# comms_sys_schematic_V2.net
KiCad netlist of a schematic drawn in EAGLE
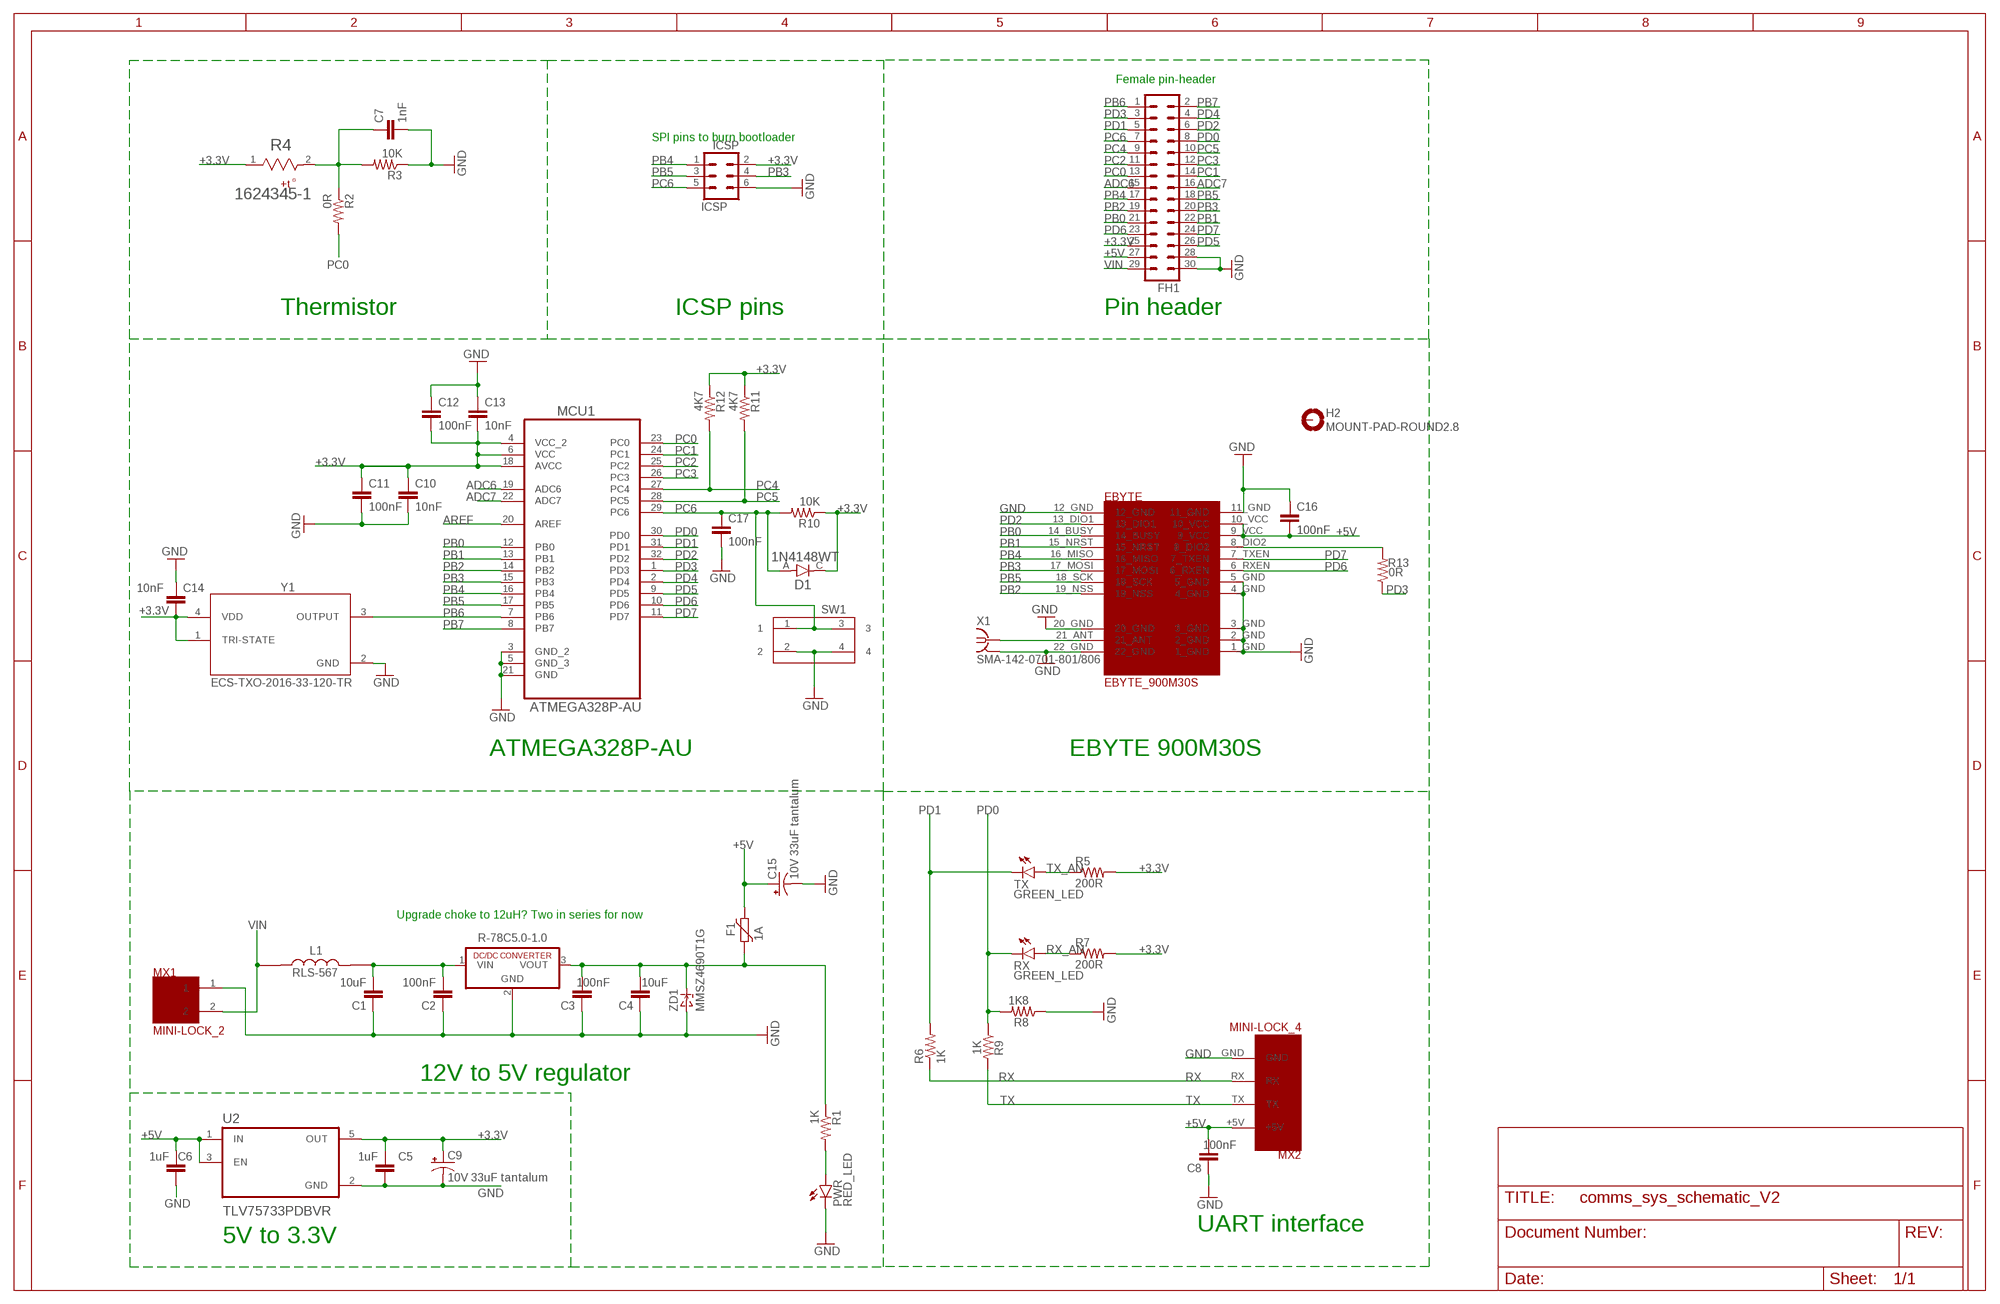
[diagram p0: schematic, sheet 1]

(export (version "E")
  (design (tool "Eeschema 10.0.6"))
  (components
    (comp (ref "C1")
      (value "10uF")
      (footprint "eagle-import:C0805")
      (libsource (lib "eagle-import") (part "C-EUC0805"))
    )
    (comp (ref "C2")
      (value "100nF")
      (footprint "eagle-import:C0805")
      (libsource (lib "eagle-import") (part "C-EUC0805"))
    )
    (comp (ref "C3")
      (value "100nF")
      (footprint "eagle-import:C0805")
      (libsource (lib "eagle-import") (part "C-EUC0805"))
    )
    (comp (ref "C4")
      (value "10uF")
      (footprint "eagle-import:C0805")
      (libsource (lib "eagle-import") (part "C-EUC0805"))
    )
    (comp (ref "C5")
      (value "1uF")
      (footprint "eagle-import:C0805")
      (libsource (lib "eagle-import") (part "C-EUC0805"))
    )
    (comp (ref "C6")
      (value "1uF")
      (footprint "eagle-import:C0805")
      (libsource (lib "eagle-import") (part "C-EUC0805"))
    )
    (comp (ref "C7")
      (value "1nF")
      (footprint "eagle-import:C0805")
      (libsource (lib "eagle-import") (part "C-EUC0805"))
    )
    (comp (ref "C8")
      (value "100nF")
      (footprint "eagle-import:C0805")
      (libsource (lib "eagle-import") (part "C-EUC0805"))
    )
    (comp (ref "C9")
      (value "10V 33uF tantalum")
      (footprint "eagle-import:CT3216")
      (libsource (lib "eagle-import") (part "CPOL-USCT3216"))
    )
    (comp (ref "C10")
      (value "10nF")
      (footprint "eagle-import:C0805")
      (libsource (lib "eagle-import") (part "C-EUC0805"))
    )
    (comp (ref "C11")
      (value "100nF")
      (footprint "eagle-import:C0805")
      (libsource (lib "eagle-import") (part "C-EUC0805"))
    )
    (comp (ref "C12")
      (value "100nF")
      (footprint "eagle-import:C0805")
      (libsource (lib "eagle-import") (part "C-EUC0805"))
    )
    (comp (ref "C13")
      (value "10nF")
      (footprint "eagle-import:C0805")
      (libsource (lib "eagle-import") (part "C-EUC0805"))
    )
    (comp (ref "C14")
      (value "10nF")
      (footprint "eagle-import:C0805")
      (libsource (lib "eagle-import") (part "C-EUC0805"))
    )
    (comp (ref "C15")
      (value "10V 33uF tantalum")
      (footprint "eagle-import:CT3216")
      (libsource (lib "eagle-import") (part "CPOL-USCT3216"))
    )
    (comp (ref "C16")
      (value "100nF")
      (footprint "eagle-import:C0805")
      (libsource (lib "eagle-import") (part "C-EUC0805"))
    )
    (comp (ref "C17")
      (value "100nF")
      (footprint "eagle-import:C0805")
      (libsource (lib "eagle-import") (part "C-EUC0805"))
    )
    (comp (ref "D1")
      (value "1N4148WT")
      (footprint "eagle-import:SODFL1608X70N")
      (fields (field (name "DIGI-KEY_PART_NUMBER") "1N4148WTCT-ND") (field (name "MF") "ON Semiconductor"))
      (libsource (lib "eagle-import") (part "1N4148WT"))
    )
    (comp (ref "EBYTE")
      (value "EBYTE_900M30S")
      (footprint "eagle-import:EBYTE_SX1262_900M30S_FOOTPRINT")
      (libsource (lib "eagle-import") (part "EBYTE_SX1262_900M30S"))
    )
    (comp (ref "F1")
      (value "1A")
      (footprint "eagle-import:PTC0805")
      (libsource (lib "eagle-import") (part "FUSE_PTC-0805"))
    )
    (comp (ref "FH1")
      (value "MA15-2")
      (footprint "eagle-import:MA15-2")
      (libsource (lib "eagle-import") (part "MA15-2"))
    )
    (comp (ref "H2")
      (value "MOUNT-PAD-ROUND2.8")
      (footprint "eagle-import:2,8-PAD")
      (libsource (lib "eagle-import") (part "MOUNT-PAD-ROUND2.8"))
    )
    (comp (ref "ICSP")
      (value "ICSP")
      (footprint "eagle-import:MA03-2")
      (libsource (lib "eagle-import") (part "MA03-2"))
    )
    (comp (ref "L1")
      (value "RLS-567")
      (footprint "eagle-import:IND_RLS-567")
      (fields (field (name "MF") "Recom Power"))
      (libsource (lib "eagle-import") (part "RLS-567"))
    )
    (comp (ref "MCU1")
      (value "ATMEGA328P-AU")
      (footprint "eagle-import:QFP80P900X900X120-32N")
      (libsource (lib "eagle-import") (part "ATMEGA328P-AU"))
    )
    (comp (ref "MX1")
      (value "MINI-LOCK_2")
      (footprint "eagle-import:MINI-LOCK_2")
      (libsource (lib "eagle-import") (part "MINI-LOCK_2"))
    )
    (comp (ref "MX2")
      (value "MINI-LOCK_4")
      (footprint "eagle-import:MINI-LOCK_4")
      (libsource (lib "eagle-import") (part "MINI-LOCK_4"))
    )
    (comp (ref "PWR")
      (value "RED_LED")
      (footprint "eagle-import:CHIP-LED0805")
      (libsource (lib "eagle-import") (part "LEDCHIP-LED0805"))
    )
    (comp (ref "R1")
      (value "1K")
      (footprint "eagle-import:R0805")
      (libsource (lib "eagle-import") (part "R-US_R0805"))
    )
    (comp (ref "R2")
      (value "0R")
      (footprint "eagle-import:R0805")
      (libsource (lib "eagle-import") (part "R-US_R0805"))
    )
    (comp (ref "R3")
      (value "10K")
      (footprint "eagle-import:R0805")
      (libsource (lib "eagle-import") (part "R-US_R0805"))
    )
    (comp (ref "R4")
      (value "1624345-1")
      (footprint "eagle-import:THRMC2012X50N")
      (fields
        (field (name "DIGI-KEY_PART_NUMBER") "A106104CT-ND")
        (field (name "MF") "TE Connectivity")
        (field (name "MP") "NTC0805J10K")
      )
      (libsource (lib "eagle-import") (part "1624345-1"))
    )
    (comp (ref "R5")
      (value "200R")
      (footprint "eagle-import:R0805")
      (libsource (lib "eagle-import") (part "R-US_R0805"))
    )
    (comp (ref "R6")
      (value "1K")
      (footprint "eagle-import:R0805")
      (libsource (lib "eagle-import") (part "R-US_R0805"))
    )
    (comp (ref "R7")
      (value "200R")
      (footprint "eagle-import:R0805")
      (libsource (lib "eagle-import") (part "R-US_R0805"))
    )
    (comp (ref "R8")
      (value "1K8")
      (footprint "eagle-import:R0805")
      (libsource (lib "eagle-import") (part "R-US_R0805"))
    )
    (comp (ref "R9")
      (value "1K")
      (footprint "eagle-import:R0805")
      (libsource (lib "eagle-import") (part "R-US_R0805"))
    )
    (comp (ref "R10")
      (value "10K")
      (footprint "eagle-import:R0805")
      (libsource (lib "eagle-import") (part "R-US_R0805"))
    )
    (comp (ref "R11")
      (value "4K7")
      (footprint "eagle-import:R0805")
      (libsource (lib "eagle-import") (part "R-US_R0805"))
    )
    (comp (ref "R12")
      (value "4K7")
      (footprint "eagle-import:R0805")
      (libsource (lib "eagle-import") (part "R-US_R0805"))
    )
    (comp (ref "R13")
      (value "0R")
      (footprint "eagle-import:R0805")
      (libsource (lib "eagle-import") (part "R-US_R0805"))
    )
    (comp (ref "RX")
      (value "GREEN_LED")
      (footprint "eagle-import:CHIP-LED0805")
      (libsource (lib "eagle-import") (part "LEDCHIP-LED0805"))
    )
    (comp (ref "SW1")
      (value "430152043826")
      (footprint "eagle-import:430152043826")
      (libsource (lib "eagle-import") (part "430152043826"))
    )
    (comp (ref "TX")
      (value "GREEN_LED")
      (footprint "eagle-import:CHIP-LED0805")
      (libsource (lib "eagle-import") (part "LEDCHIP-LED0805"))
    )
    (comp (ref "U1")
      (value "R-78C5.0-1.0")
      (footprint "eagle-import:SIP3")
      (libsource (lib "eagle-import") (part "R-78C-1.05.0"))
    )
    (comp (ref "U2")
      (value "TLV75733PDBVR")
      (footprint "eagle-import:SOT95P280X145-5N")
      (fields (field (name "DIGI-KEY_PART_NUMBER") "296-50414-1-ND") (field (name "MF") "Texas Instruments"))
      (libsource (lib "eagle-import") (part "TLV75733PDBVR"))
    )
    (comp (ref "X1")
      (value "SMA-142-0701-801/806")
      (footprint "eagle-import:J502-ND-142-0701-801_806")
      (fields (field (name "MF") "JOHNSON COMPONENTS") (field (name "MPN") "142-0701-801"))
      (libsource (lib "eagle-import") (part "SMA-142-0701-801/806"))
    )
    (comp (ref "Y1")
      (value "ECS-TXO-2016-33-120-TR")
      (footprint "eagle-import:OSC_ECS-TXO-2016-33-120-TR")
      (fields (field (name "DIGI-KEY_PART_NUMBER") "XC3160CT-ND") (field (name "MF") "ECS Inc."))
      (libsource (lib "eagle-import") (part "ECS-TXO-2016-33-120-TR"))
    )
    (comp (ref "ZD1")
      (value "MMSZ4690T1G")
      (footprint "eagle-import:SOD-123")
      (libsource (lib "eagle-import") (part "ZENERSOD-123"))
    )
  )
  (nets
    (net (code "1") (name "/+3.3V") (class "Default")
      (node (ref "C10") (pin "1") (pinfunction "1_1") (pintype "passive"))
      (node (ref "C11") (pin "1") (pinfunction "1_1") (pintype "passive"))
      (node (ref "C12") (pin "2") (pinfunction "2_2") (pintype "passive"))
      (node (ref "C13") (pin "2") (pinfunction "2_2") (pintype "passive"))
      (node (ref "C14") (pin "2") (pinfunction "2_2") (pintype "passive"))
      (node (ref "C5") (pin "2") (pinfunction "2_2") (pintype "passive"))
      (node (ref "C9") (pin "+") (pinfunction "+_+") (pintype "passive"))
      (node (ref "D1") (pin "C") (pinfunction "C_C") (pintype "passive"))
      (node (ref "FH1") (pin "25") (pinfunction "29_25") (pintype "passive"))
      (node (ref "ICSP") (pin "2") (pinfunction "2_2") (pintype "passive"))
      (node (ref "MCU1") (pin "18") (pinfunction "AVCC_18") (pintype "power_in"))
      (node (ref "MCU1") (pin "4") (pinfunction "VCC_2_4") (pintype "power_in"))
      (node (ref "MCU1") (pin "6") (pinfunction "VCC_6") (pintype "power_in"))
      (node (ref "R10") (pin "1") (pinfunction "1_1") (pintype "passive"))
      (node (ref "R11") (pin "1") (pinfunction "1_1") (pintype "passive"))
      (node (ref "R12") (pin "1") (pinfunction "1_1") (pintype "passive"))
      (node (ref "R4") (pin "1") (pinfunction "1_1") (pintype "passive"))
      (node (ref "R5") (pin "2") (pinfunction "2_2") (pintype "passive"))
      (node (ref "R7") (pin "2") (pinfunction "2_2") (pintype "passive"))
      (node (ref "U2") (pin "5") (pinfunction "OUT_5") (pintype "output"))
      (node (ref "Y1") (pin "1") (pinfunction "TRI-STATE_1") (pintype "input"))
      (node (ref "Y1") (pin "4") (pinfunction "VDD_4") (pintype "input"))
    )
    (net (code "2") (name "/+5V") (class "Default")
      (node (ref "C15") (pin "+") (pinfunction "+_+") (pintype "passive"))
      (node (ref "C16") (pin "2") (pinfunction "2_2") (pintype "passive"))
      (node (ref "C6") (pin "2") (pinfunction "2_2") (pintype "passive"))
      (node (ref "C8") (pin "2") (pinfunction "2_2") (pintype "passive"))
      (node (ref "EBYTE") (pin "10_VCC") (pinfunction "10_VCC_10_VCC") (pintype "power_in"))
      (node (ref "EBYTE") (pin "9_VCC") (pinfunction "9_VCC_9_VCC") (pintype "power_in"))
      (node (ref "F1") (pin "2") (pinfunction "2_2") (pintype "passive"))
      (node (ref "FH1") (pin "27") (pinfunction "31_27") (pintype "passive"))
      (node (ref "MX2") (pin "+5V") (pinfunction "+5V_+5V") (pintype "bidirectional"))
      (node (ref "U2") (pin "1") (pinfunction "IN_1") (pintype "input"))
      (node (ref "U2") (pin "3") (pinfunction "EN_3") (pintype "bidirectional"))
    )
    (net (code "3") (name "/ADC6") (class "Default")
      (node (ref "FH1") (pin "15") (pinfunction "19_15") (pintype "passive"))
      (node (ref "MCU1") (pin "19") (pinfunction "ADC6_19") (pintype "input"))
    )
    (net (code "4") (name "/ADC7") (class "Default")
      (node (ref "FH1") (pin "16") (pinfunction "20_16") (pintype "passive"))
      (node (ref "MCU1") (pin "22") (pinfunction "ADC7_22") (pintype "input"))
    )
    (net (code "5") (name "/AREF") (class "Default")
      (node (ref "MCU1") (pin "20") (pinfunction "AREF_20") (pintype "input"))
    )
    (net (code "6") (name "/PB0") (class "Default")
      (node (ref "EBYTE") (pin "14_BUSY") (pinfunction "14_BUSY_14_BUSY") (pintype "bidirectional"))
      (node (ref "FH1") (pin "21") (pinfunction "25_21") (pintype "passive"))
      (node (ref "MCU1") (pin "12") (pinfunction "PB0_12") (pintype "bidirectional"))
    )
    (net (code "7") (name "/PB1") (class "Default")
      (node (ref "EBYTE") (pin "15_NRST") (pinfunction "15_NRST_15_NRST") (pintype "bidirectional"))
      (node (ref "FH1") (pin "22") (pinfunction "26_22") (pintype "passive"))
      (node (ref "MCU1") (pin "13") (pinfunction "PB1_13") (pintype "bidirectional"))
    )
    (net (code "8") (name "/PB2") (class "Default")
      (node (ref "EBYTE") (pin "19_NSS") (pinfunction "19_NSS_19_NSS") (pintype "bidirectional"))
      (node (ref "FH1") (pin "19") (pinfunction "23_19") (pintype "passive"))
      (node (ref "MCU1") (pin "14") (pinfunction "PB2_14") (pintype "bidirectional"))
    )
    (net (code "9") (name "/PB3") (class "Default")
      (node (ref "EBYTE") (pin "17_MOSI") (pinfunction "17_MOSI_17_MOSI") (pintype "bidirectional"))
      (node (ref "FH1") (pin "20") (pinfunction "24_20") (pintype "passive"))
      (node (ref "ICSP") (pin "4") (pinfunction "4_4") (pintype "passive"))
      (node (ref "MCU1") (pin "15") (pinfunction "PB3_15") (pintype "bidirectional"))
    )
    (net (code "10") (name "/PB4") (class "Default")
      (node (ref "EBYTE") (pin "16_MISO") (pinfunction "16_MISO_16_MISO") (pintype "bidirectional"))
      (node (ref "FH1") (pin "17") (pinfunction "21_17") (pintype "passive"))
      (node (ref "ICSP") (pin "1") (pinfunction "1_1") (pintype "passive"))
      (node (ref "MCU1") (pin "16") (pinfunction "PB4_16") (pintype "bidirectional"))
    )
    (net (code "11") (name "/PB5") (class "Default")
      (node (ref "EBYTE") (pin "18_SCK") (pinfunction "18_SCK_18_SCK") (pintype "bidirectional"))
      (node (ref "FH1") (pin "18") (pinfunction "22_18") (pintype "passive"))
      (node (ref "ICSP") (pin "3") (pinfunction "3_3") (pintype "passive"))
      (node (ref "MCU1") (pin "17") (pinfunction "PB5_17") (pintype "bidirectional"))
    )
    (net (code "12") (name "/PB6") (class "Default")
      (node (ref "FH1") (pin "1") (pinfunction "5_1") (pintype "passive"))
      (node (ref "MCU1") (pin "7") (pinfunction "PB6_7") (pintype "bidirectional"))
      (node (ref "Y1") (pin "3") (pinfunction "OUTPUT_3") (pintype "output"))
    )
    (net (code "13") (name "/PB7") (class "Default")
      (node (ref "FH1") (pin "2") (pinfunction "6_2") (pintype "passive"))
      (node (ref "MCU1") (pin "8") (pinfunction "PB7_8") (pintype "bidirectional"))
    )
    (net (code "14") (name "/PC0") (class "Default")
      (node (ref "FH1") (pin "13") (pinfunction "17_13") (pintype "passive"))
      (node (ref "MCU1") (pin "23") (pinfunction "PC0_23") (pintype "bidirectional"))
      (node (ref "R2") (pin "2") (pinfunction "2_2") (pintype "passive"))
    )
    (net (code "15") (name "/PC1") (class "Default")
      (node (ref "FH1") (pin "14") (pinfunction "18_14") (pintype "passive"))
      (node (ref "MCU1") (pin "24") (pinfunction "PC1_24") (pintype "bidirectional"))
    )
    (net (code "16") (name "/PC2") (class "Default")
      (node (ref "FH1") (pin "11") (pinfunction "15_11") (pintype "passive"))
      (node (ref "MCU1") (pin "25") (pinfunction "PC2_25") (pintype "bidirectional"))
    )
    (net (code "17") (name "/PC3") (class "Default")
      (node (ref "FH1") (pin "12") (pinfunction "16_12") (pintype "passive"))
      (node (ref "MCU1") (pin "26") (pinfunction "PC3_26") (pintype "bidirectional"))
    )
    (net (code "18") (name "/PC4") (class "Default")
      (node (ref "FH1") (pin "9") (pinfunction "13_9") (pintype "passive"))
      (node (ref "MCU1") (pin "27") (pinfunction "PC4_27") (pintype "bidirectional"))
      (node (ref "R12") (pin "2") (pinfunction "2_2") (pintype "passive"))
    )
    (net (code "19") (name "/PC5") (class "Default")
      (node (ref "FH1") (pin "10") (pinfunction "14_10") (pintype "passive"))
      (node (ref "MCU1") (pin "28") (pinfunction "PC5_28") (pintype "bidirectional"))
      (node (ref "R11") (pin "2") (pinfunction "2_2") (pintype "passive"))
    )
    (net (code "20") (name "/PC6") (class "Default")
      (node (ref "C17") (pin "1") (pinfunction "1_1") (pintype "passive"))
      (node (ref "D1") (pin "A") (pinfunction "A_A") (pintype "passive"))
      (node (ref "FH1") (pin "7") (pinfunction "11_7") (pintype "passive"))
      (node (ref "ICSP") (pin "5") (pinfunction "5_5") (pintype "passive"))
      (node (ref "MCU1") (pin "29") (pinfunction "PC6_29") (pintype "bidirectional"))
      (node (ref "R10") (pin "2") (pinfunction "2_2") (pintype "passive"))
      (node (ref "SW1") (pin "1") (pinfunction "1_1") (pintype "bidirectional"))
      (node (ref "SW1") (pin "3") (pinfunction "3_3") (pintype "bidirectional"))
    )
    (net (code "21") (name "/PD0") (class "Default")
      (node (ref "FH1") (pin "8") (pinfunction "12_8") (pintype "passive"))
      (node (ref "MCU1") (pin "30") (pinfunction "PD0_30") (pintype "bidirectional"))
      (node (ref "R8") (pin "2") (pinfunction "2_2") (pintype "passive"))
      (node (ref "R9") (pin "1") (pinfunction "1_1") (pintype "passive"))
      (node (ref "RX") (pin "C") (pinfunction "C_C") (pintype "passive"))
    )
    (net (code "22") (name "/PD1") (class "Default")
      (node (ref "FH1") (pin "5") (pinfunction "9_5") (pintype "passive"))
      (node (ref "MCU1") (pin "31") (pinfunction "PD1_31") (pintype "bidirectional"))
      (node (ref "R6") (pin "2") (pinfunction "2_2") (pintype "passive"))
      (node (ref "TX") (pin "C") (pinfunction "C_C") (pintype "passive"))
    )
    (net (code "23") (name "/PD2") (class "Default")
      (node (ref "EBYTE") (pin "13_DIO1") (pinfunction "13_DIO1_13_DIO1") (pintype "bidirectional"))
      (node (ref "FH1") (pin "6") (pinfunction "10_6") (pintype "passive"))
      (node (ref "MCU1") (pin "32") (pinfunction "PD2_32") (pintype "bidirectional"))
    )
    (net (code "24") (name "/PD3") (class "Default")
      (node (ref "FH1") (pin "3") (pinfunction "7_3") (pintype "passive"))
      (node (ref "MCU1") (pin "1") (pinfunction "PD3_1") (pintype "bidirectional"))
      (node (ref "R13") (pin "1") (pinfunction "1_1") (pintype "passive"))
    )
    (net (code "25") (name "/PD4") (class "Default")
      (node (ref "FH1") (pin "4") (pinfunction "8_4") (pintype "passive"))
      (node (ref "MCU1") (pin "2") (pinfunction "PD4_2") (pintype "bidirectional"))
    )
    (net (code "26") (name "/PD5") (class "Default")
      (node (ref "FH1") (pin "26") (pinfunction "30_26") (pintype "passive"))
      (node (ref "MCU1") (pin "9") (pinfunction "PD5_9") (pintype "bidirectional"))
    )
    (net (code "27") (name "/PD6") (class "Default")
      (node (ref "EBYTE") (pin "6_RXEN") (pinfunction "6_RXEN_6_RXEN") (pintype "bidirectional"))
      (node (ref "FH1") (pin "23") (pinfunction "27_23") (pintype "passive"))
      (node (ref "MCU1") (pin "10") (pinfunction "PD6_10") (pintype "bidirectional"))
    )
    (net (code "28") (name "/PD7") (class "Default")
      (node (ref "EBYTE") (pin "7_TXEN") (pinfunction "7_TXEN_7_TXEN") (pintype "bidirectional"))
      (node (ref "FH1") (pin "24") (pinfunction "28_24") (pintype "passive"))
      (node (ref "MCU1") (pin "11") (pinfunction "PD7_11") (pintype "bidirectional"))
    )
    (net (code "29") (name "/RX") (class "Default")
      (node (ref "MX2") (pin "RX") (pinfunction "RX_RX") (pintype "bidirectional"))
      (node (ref "R6") (pin "1") (pinfunction "1_1") (pintype "passive"))
    )
    (net (code "30") (name "/RX_AN") (class "Default")
      (node (ref "R7") (pin "1") (pinfunction "1_1") (pintype "passive"))
      (node (ref "RX") (pin "A") (pinfunction "A_A") (pintype "passive"))
    )
    (net (code "31") (name "/TX") (class "Default")
      (node (ref "MX2") (pin "TX") (pinfunction "TX_TX") (pintype "bidirectional"))
      (node (ref "R9") (pin "2") (pinfunction "2_2") (pintype "passive"))
    )
    (net (code "32") (name "/TX_AN") (class "Default")
      (node (ref "R5") (pin "1") (pinfunction "1_1") (pintype "passive"))
      (node (ref "TX") (pin "A") (pinfunction "A_A") (pintype "passive"))
    )
    (net (code "33") (name "/VIN") (class "Default")
      (node (ref "FH1") (pin "29") (pinfunction "33_29") (pintype "passive"))
      (node (ref "L1") (pin "1") (pinfunction "1_1") (pintype "passive"))
      (node (ref "MX1") (pin "2") (pinfunction "2_2") (pintype "bidirectional"))
    )
    (net (code "34") (name "GND") (class "Default")
      (node (ref "C1") (pin "1") (pinfunction "1_1") (pintype "passive"))
      (node (ref "C10") (pin "2") (pinfunction "2_2") (pintype "passive"))
      (node (ref "C11") (pin "2") (pinfunction "2_2") (pintype "passive"))
      (node (ref "C12") (pin "1") (pinfunction "1_1") (pintype "passive"))
      (node (ref "C13") (pin "1") (pinfunction "1_1") (pintype "passive"))
      (node (ref "C14") (pin "1") (pinfunction "1_1") (pintype "passive"))
      (node (ref "C15") (pin "-") (pinfunction "-_-") (pintype "passive"))
      (node (ref "C16") (pin "1") (pinfunction "1_1") (pintype "passive"))
      (node (ref "C17") (pin "2") (pinfunction "2_2") (pintype "passive"))
      (node (ref "C2") (pin "1") (pinfunction "1_1") (pintype "passive"))
      (node (ref "C3") (pin "1") (pinfunction "1_1") (pintype "passive"))
      (node (ref "C4") (pin "1") (pinfunction "1_1") (pintype "passive"))
      (node (ref "C5") (pin "1") (pinfunction "1_1") (pintype "passive"))
      (node (ref "C6") (pin "1") (pinfunction "1_1") (pintype "passive"))
      (node (ref "C7") (pin "2") (pinfunction "2_2") (pintype "passive"))
      (node (ref "C8") (pin "1") (pinfunction "1_1") (pintype "passive"))
      (node (ref "C9") (pin "-") (pinfunction "-_-") (pintype "passive"))
      (node (ref "EBYTE") (pin "11_GND") (pinfunction "11_GND_11_GND") (pintype "power_in"))
      (node (ref "EBYTE") (pin "12_GND") (pinfunction "12_GND_12_GND") (pintype "power_in"))
      (node (ref "EBYTE") (pin "1_GND") (pinfunction "1_GND_1_GND") (pintype "power_in"))
      (node (ref "EBYTE") (pin "20_GND") (pinfunction "20_GND_20_GND") (pintype "power_in"))
      (node (ref "EBYTE") (pin "22_GND") (pinfunction "22_GND_22_GND") (pintype "power_in"))
      (node (ref "EBYTE") (pin "2_GND") (pinfunction "2_GND_2_GND") (pintype "power_in"))
      (node (ref "EBYTE") (pin "3_GND") (pinfunction "3_GND_3_GND") (pintype "power_in"))
      (node (ref "EBYTE") (pin "4_GND") (pinfunction "4_GND_4_GND") (pintype "power_in"))
      (node (ref "EBYTE") (pin "5_GND") (pinfunction "5_GND_5_GND") (pintype "power_in"))
      (node (ref "FH1") (pin "28") (pinfunction "32_28") (pintype "passive"))
      (node (ref "FH1") (pin "30") (pinfunction "34_30") (pintype "passive"))
      (node (ref "ICSP") (pin "6") (pinfunction "6_6") (pintype "passive"))
      (node (ref "MCU1") (pin "21") (pinfunction "GND_21") (pintype "passive"))
      (node (ref "MCU1") (pin "3") (pinfunction "GND_2_3") (pintype "passive"))
      (node (ref "MCU1") (pin "5") (pinfunction "GND_3_5") (pintype "passive"))
      (node (ref "MX1") (pin "1") (pinfunction "1_1") (pintype "bidirectional"))
      (node (ref "MX2") (pin "GND") (pinfunction "GND_GND") (pintype "bidirectional"))
      (node (ref "PWR") (pin "C") (pinfunction "C_C") (pintype "passive"))
      (node (ref "R3") (pin "1") (pinfunction "1_1") (pintype "passive"))
      (node (ref "R8") (pin "1") (pinfunction "1_1") (pintype "passive"))
      (node (ref "SW1") (pin "2") (pinfunction "2_2") (pintype "bidirectional"))
      (node (ref "SW1") (pin "4") (pinfunction "4_4") (pintype "bidirectional"))
      (node (ref "U1") (pin "2") (pinfunction "GND_2") (pintype "passive"))
      (node (ref "U2") (pin "2") (pinfunction "GND_2") (pintype "power_in"))
      (node (ref "X1") (pin "G@1") (pinfunction "2_G@1") (pintype "passive"))
      (node (ref "X1") (pin "G@2") (pinfunction "2_G@2") (pintype "passive"))
      (node (ref "X1") (pin "G@3") (pinfunction "2_G@3") (pintype "passive"))
      (node (ref "X1") (pin "G@4") (pinfunction "2_G@4") (pintype "passive"))
      (node (ref "Y1") (pin "2") (pinfunction "GND_2") (pintype "power_in"))
      (node (ref "ZD1") (pin "A") (pinfunction "A_A") (pintype "passive"))
    )
    (net (code "35") (name "Net-(C7-Pad1)") (class "Default")
      (node (ref "C7") (pin "1") (pinfunction "1_1") (pintype "passive"))
      (node (ref "R2") (pin "1") (pinfunction "1_1") (pintype "passive"))
      (node (ref "R3") (pin "2") (pinfunction "2_2") (pintype "passive"))
      (node (ref "R4") (pin "2") (pinfunction "2_2") (pintype "passive"))
    )
    (net (code "36") (name "Net-(EBYTE-Pad8_DIO2)") (class "Default")
      (node (ref "EBYTE") (pin "8_DIO2") (pinfunction "8_DIO2_8_DIO2") (pintype "bidirectional"))
      (node (ref "R13") (pin "2") (pinfunction "2_2") (pintype "passive"))
    )
    (net (code "37") (name "Net-(EBYTE-Pad21_ANT)") (class "Default")
      (node (ref "EBYTE") (pin "21_ANT") (pinfunction "21_ANT_21_ANT") (pintype "bidirectional"))
      (node (ref "X1") (pin "1") (pinfunction "1_1") (pintype "passive"))
    )
    (net (code "38") (name "Net-(PWR-PadA)") (class "Default")
      (node (ref "PWR") (pin "A") (pinfunction "A_A") (pintype "passive"))
      (node (ref "R1") (pin "2") (pinfunction "2_2") (pintype "passive"))
    )
    (net (code "39") (name "Net-(U1-VIN)") (class "Default")
      (node (ref "C1") (pin "2") (pinfunction "2_2") (pintype "passive"))
      (node (ref "C2") (pin "2") (pinfunction "2_2") (pintype "passive"))
      (node (ref "L1") (pin "2") (pinfunction "2_2") (pintype "passive"))
      (node (ref "U1") (pin "1") (pinfunction "VIN_1") (pintype "passive"))
    )
    (net (code "40") (name "Net-(U1-VOUT)") (class "Default")
      (node (ref "C3") (pin "2") (pinfunction "2_2") (pintype "passive"))
      (node (ref "C4") (pin "2") (pinfunction "2_2") (pintype "passive"))
      (node (ref "F1") (pin "1") (pinfunction "1_1") (pintype "passive"))
      (node (ref "R1") (pin "1") (pinfunction "1_1") (pintype "passive"))
      (node (ref "U1") (pin "3") (pinfunction "VOUT_3") (pintype "passive"))
      (node (ref "ZD1") (pin "C") (pinfunction "C_C") (pintype "passive"))
    )
    (net (code "41") (name "unconnected-(H2-MOUNT-PadB2,8)") (class "Default")
      (node (ref "H2") (pin "B2,8") (pinfunction "MOUNT_B2,8") (pintype "passive"))
    )
  )
)
